# asserv.net
KiCad netlist of a schematic drawn in EAGLE
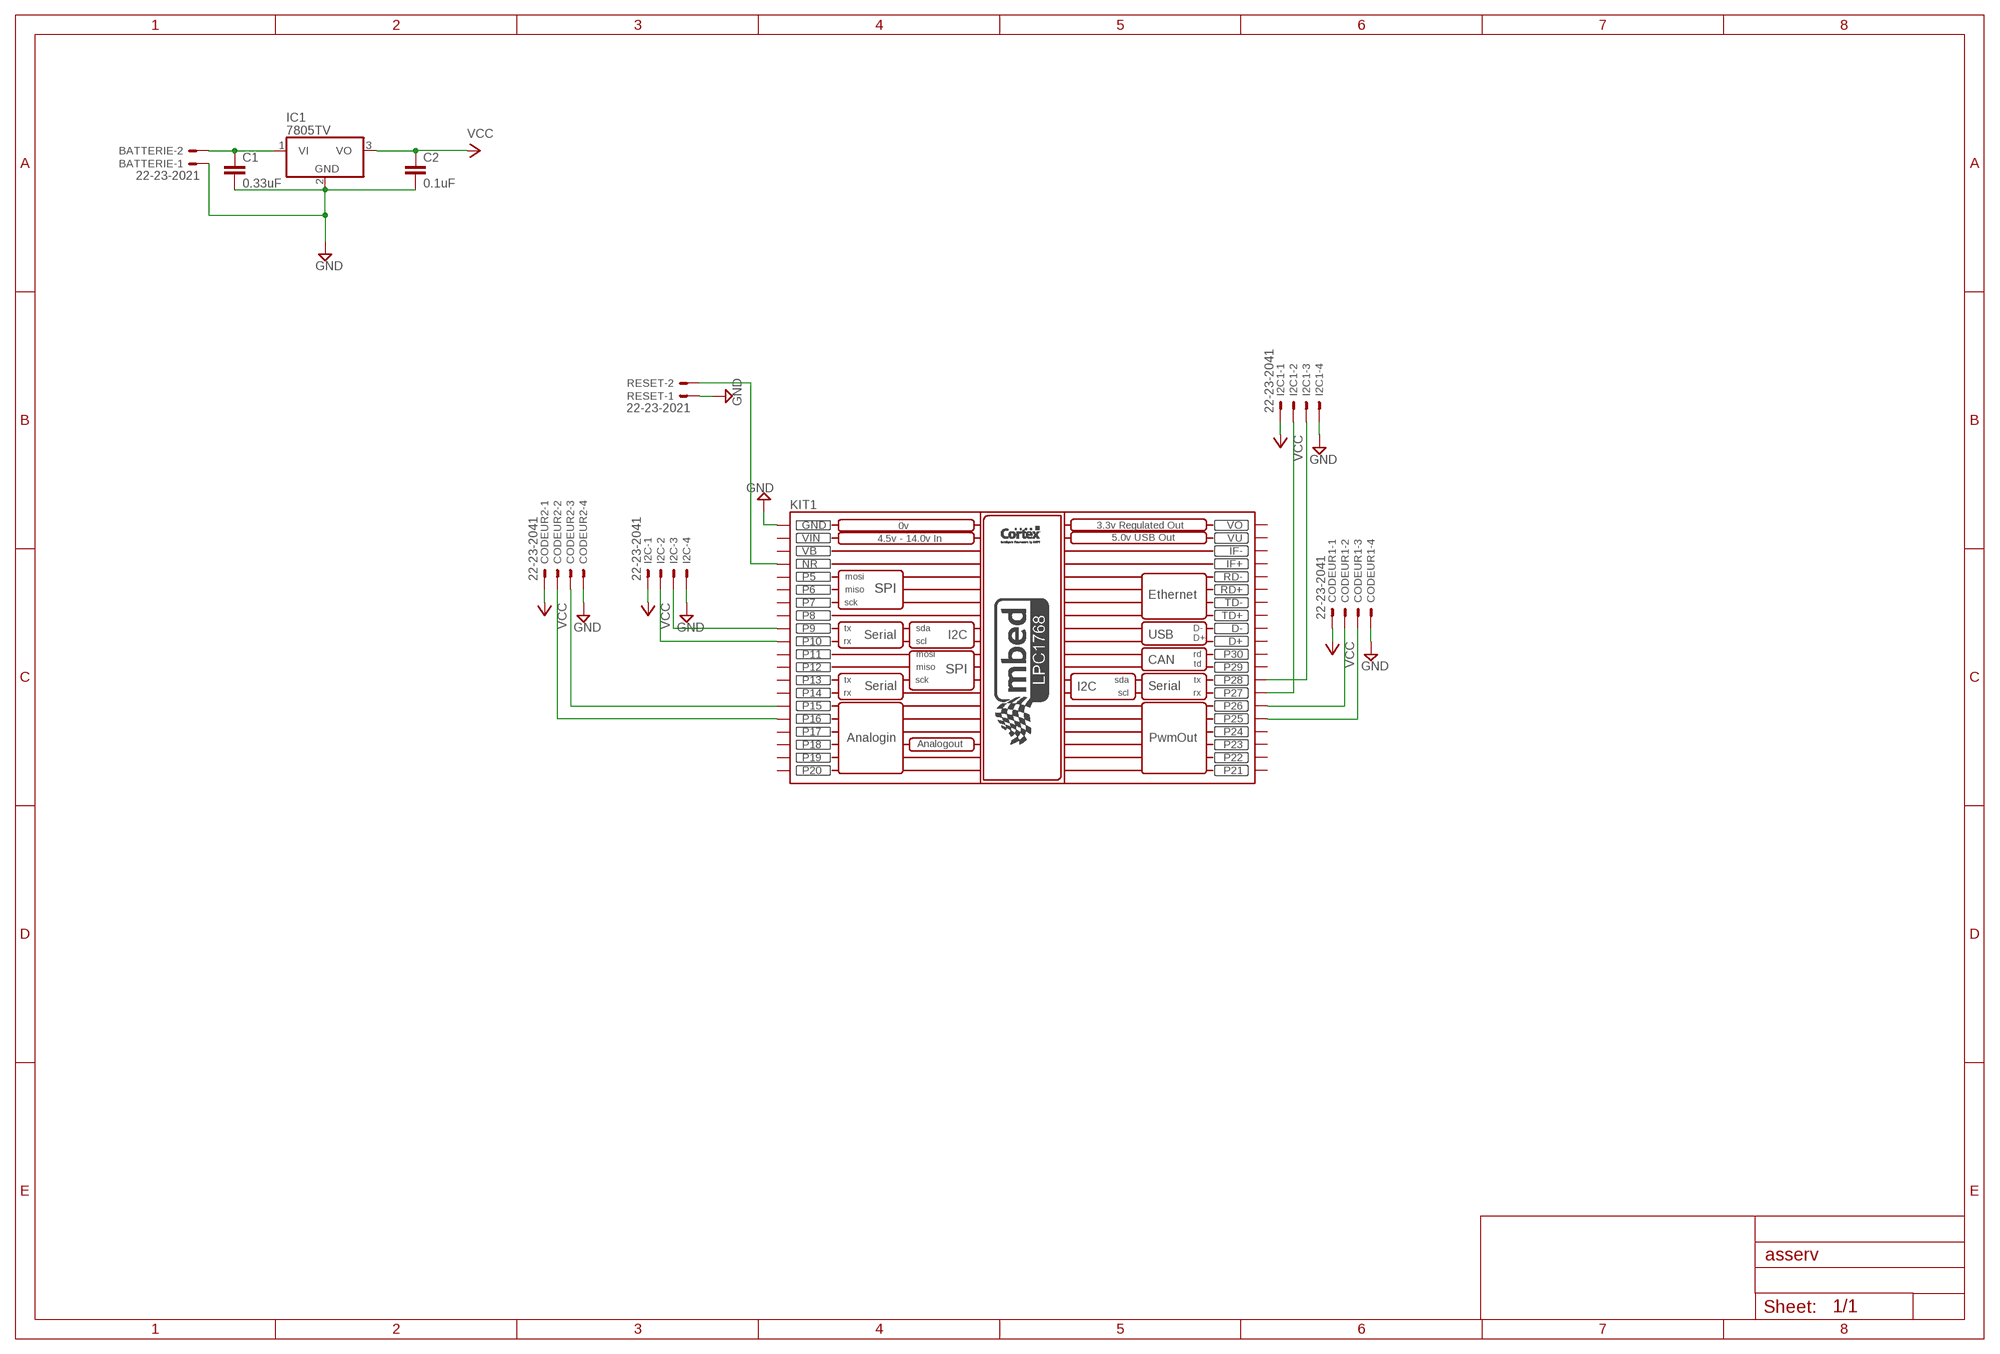
[diagram p0: schematic, sheet 1]

(export (version "E")
  (design (tool "Eeschema 10.0.6"))
  (components
    (comp (ref "BATTERIE")
      (value "22-23-2021")
      (footprint "eagle-import:22-23-2021")
      (fields (field (name "MF") "MOLEX"))
      (libsource (lib "eagle-import") (part "22-23-2021"))
    )
    (comp (ref "C1")
      (value "0.33uF")
      (footprint "eagle-import:C5B2.5")
      (libsource (lib "eagle-import") (part "C5/2.5"))
    )
    (comp (ref "C2")
      (value "0.1uF")
      (footprint "eagle-import:C5B2.5")
      (libsource (lib "eagle-import") (part "C5/2.5"))
    )
    (comp (ref "CODEUR1")
      (value "22-23-2041")
      (footprint "eagle-import:22-23-2041")
      (fields (field (name "MF") "MOLEX"))
      (libsource (lib "eagle-import") (part "22-23-2041"))
    )
    (comp (ref "CODEUR2")
      (value "22-23-2041")
      (footprint "eagle-import:22-23-2041")
      (fields (field (name "MF") "MOLEX"))
      (libsource (lib "eagle-import") (part "22-23-2041"))
    )
    (comp (ref "I2C")
      (value "22-23-2041")
      (footprint "eagle-import:22-23-2041")
      (fields (field (name "MF") "MOLEX"))
      (libsource (lib "eagle-import") (part "22-23-2041"))
    )
    (comp (ref "I2C1")
      (value "22-23-2041")
      (footprint "eagle-import:22-23-2041")
      (fields (field (name "MF") "MOLEX"))
      (libsource (lib "eagle-import") (part "22-23-2041"))
    )
    (comp (ref "IC1")
      (value "7805TV")
      (footprint "eagle-import:TO220V")
      (libsource (lib "eagle-import") (part "78TV05"))
    )
    (comp (ref "KIT1")
      (value "MBED_NXP_LPC1768")
      (footprint "eagle-import:MBED-KIT")
      (libsource (lib "eagle-import") (part "MBED_NXP_LPC1768"))
    )
    (comp (ref "RESET")
      (value "22-23-2021")
      (footprint "eagle-import:22-23-2021")
      (fields (field (name "MF") "MOLEX"))
      (libsource (lib "eagle-import") (part "22-23-2021"))
    )
  )
  (nets
    (net (code "1") (name "/VB") (class "Default")
      (node (ref "KIT1") (pin "VB") (pinfunction "VB_VB") (pintype "power_in"))
    )
    (net (code "2") (name "/VIN") (class "Default")
      (node (ref "KIT1") (pin "VIN") (pinfunction "VIN_VIN") (pintype "power_in"))
    )
    (net (code "3") (name "/VO") (class "Default")
      (node (ref "KIT1") (pin "VOUT") (pinfunction "VO_VOUT") (pintype "power_in"))
    )
    (net (code "4") (name "/VU") (class "Default")
      (node (ref "KIT1") (pin "VU") (pinfunction "VU_VU") (pintype "power_in"))
    )
    (net (code "5") (name "GND") (class "Default")
      (node (ref "BATTERIE") (pin "1") (pinfunction "S_1") (pintype "passive"))
      (node (ref "C1") (pin "2") (pinfunction "2_2") (pintype "passive"))
      (node (ref "C2") (pin "2") (pinfunction "2_2") (pintype "passive"))
      (node (ref "CODEUR1") (pin "4") (pinfunction "S_4") (pintype "passive"))
      (node (ref "CODEUR2") (pin "4") (pinfunction "S_4") (pintype "passive"))
      (node (ref "I2C") (pin "4") (pinfunction "S_4") (pintype "passive"))
      (node (ref "I2C1") (pin "4") (pinfunction "S_4") (pintype "passive"))
      (node (ref "IC1") (pin "2") (pinfunction "GND_2") (pintype "passive"))
      (node (ref "KIT1") (pin "GND") (pinfunction "GND_GND") (pintype "power_in"))
      (node (ref "RESET") (pin "1") (pinfunction "S_1") (pintype "passive"))
    )
    (net (code "6") (name "Net-(BATTERIEB-S)") (class "Default")
      (node (ref "BATTERIE") (pin "2") (pinfunction "S_2") (pintype "passive"))
      (node (ref "C1") (pin "1") (pinfunction "1_1") (pintype "passive"))
      (node (ref "IC1") (pin "1") (pinfunction "VI_1") (pintype "input"))
    )
    (net (code "7") (name "Net-(CODEUR1B-S)") (class "Default")
      (node (ref "CODEUR1") (pin "2") (pinfunction "S_2") (pintype "passive"))
      (node (ref "KIT1") (pin "P$26") (pinfunction "P26_P$26") (pintype "bidirectional"))
    )
    (net (code "8") (name "Net-(CODEUR1C-S)") (class "Default")
      (node (ref "CODEUR1") (pin "3") (pinfunction "S_3") (pintype "passive"))
      (node (ref "KIT1") (pin "P$25") (pinfunction "P25_P$25") (pintype "bidirectional"))
    )
    (net (code "9") (name "Net-(CODEUR2B-S)") (class "Default")
      (node (ref "CODEUR2") (pin "2") (pinfunction "S_2") (pintype "passive"))
      (node (ref "KIT1") (pin "P$16") (pinfunction "P16_P$16") (pintype "bidirectional"))
    )
    (net (code "10") (name "Net-(CODEUR2C-S)") (class "Default")
      (node (ref "CODEUR2") (pin "3") (pinfunction "S_3") (pintype "passive"))
      (node (ref "KIT1") (pin "P$15") (pinfunction "P15_P$15") (pintype "bidirectional"))
    )
    (net (code "11") (name "Net-(I2C1B-S)") (class "Default")
      (node (ref "I2C1") (pin "2") (pinfunction "S_2") (pintype "passive"))
      (node (ref "KIT1") (pin "P$27") (pinfunction "P27_P$27") (pintype "bidirectional"))
    )
    (net (code "12") (name "Net-(I2C1C-S)") (class "Default")
      (node (ref "I2C1") (pin "3") (pinfunction "S_3") (pintype "passive"))
      (node (ref "KIT1") (pin "P$28") (pinfunction "P28_P$28") (pintype "bidirectional"))
    )
    (net (code "13") (name "Net-(I2CB-S)") (class "Default")
      (node (ref "I2C") (pin "2") (pinfunction "S_2") (pintype "passive"))
      (node (ref "KIT1") (pin "P$10") (pinfunction "P10_P$10") (pintype "bidirectional"))
    )
    (net (code "14") (name "Net-(I2CC-S)") (class "Default")
      (node (ref "I2C") (pin "3") (pinfunction "S_3") (pintype "passive"))
      (node (ref "KIT1") (pin "P$9") (pinfunction "P9_P$9") (pintype "bidirectional"))
    )
    (net (code "15") (name "Net-(RESETB-S)") (class "Default")
      (node (ref "KIT1") (pin "NR") (pinfunction "NR_NR") (pintype "power_in"))
      (node (ref "RESET") (pin "2") (pinfunction "S_2") (pintype "passive"))
    )
    (net (code "16") (name "VCC") (class "Default")
      (node (ref "C2") (pin "1") (pinfunction "1_1") (pintype "passive"))
      (node (ref "CODEUR1") (pin "1") (pinfunction "S_1") (pintype "passive"))
      (node (ref "CODEUR2") (pin "1") (pinfunction "S_1") (pintype "passive"))
      (node (ref "I2C") (pin "1") (pinfunction "S_1") (pintype "passive"))
      (node (ref "I2C1") (pin "1") (pinfunction "S_1") (pintype "passive"))
      (node (ref "IC1") (pin "3") (pinfunction "VO_3") (pintype "passive"))
    )
    (net (code "17") (name "unconnected-(KIT1-P5-PadP$5)") (class "Default")
      (node (ref "KIT1") (pin "P$5") (pinfunction "P5_P$5") (pintype "bidirectional"))
    )
    (net (code "18") (name "unconnected-(KIT1-P6-PadP$6)") (class "Default")
      (node (ref "KIT1") (pin "P$6") (pinfunction "P6_P$6") (pintype "bidirectional"))
    )
    (net (code "19") (name "unconnected-(KIT1-P7-PadP$7)") (class "Default")
      (node (ref "KIT1") (pin "P$7") (pinfunction "P7_P$7") (pintype "bidirectional"))
    )
    (net (code "20") (name "unconnected-(KIT1-P8-PadP$8)") (class "Default")
      (node (ref "KIT1") (pin "P$8") (pinfunction "P8_P$8") (pintype "bidirectional"))
    )
    (net (code "21") (name "unconnected-(KIT1-P11-PadP$11)") (class "Default")
      (node (ref "KIT1") (pin "P$11") (pinfunction "P11_P$11") (pintype "bidirectional"))
    )
    (net (code "22") (name "unconnected-(KIT1-P12-PadP$12)") (class "Default")
      (node (ref "KIT1") (pin "P$12") (pinfunction "P12_P$12") (pintype "bidirectional"))
    )
    (net (code "23") (name "unconnected-(KIT1-P13-PadP$13)") (class "Default")
      (node (ref "KIT1") (pin "P$13") (pinfunction "P13_P$13") (pintype "bidirectional"))
    )
    (net (code "24") (name "unconnected-(KIT1-P14-PadP$14)") (class "Default")
      (node (ref "KIT1") (pin "P$14") (pinfunction "P14_P$14") (pintype "bidirectional"))
    )
    (net (code "25") (name "unconnected-(KIT1-P17-PadP$17)") (class "Default")
      (node (ref "KIT1") (pin "P$17") (pinfunction "P17_P$17") (pintype "bidirectional"))
    )
    (net (code "26") (name "unconnected-(KIT1-P18-PadP$18)") (class "Default")
      (node (ref "KIT1") (pin "P$18") (pinfunction "P18_P$18") (pintype "bidirectional"))
    )
    (net (code "27") (name "unconnected-(KIT1-P19-PadP$19)") (class "Default")
      (node (ref "KIT1") (pin "P$19") (pinfunction "P19_P$19") (pintype "bidirectional"))
    )
    (net (code "28") (name "unconnected-(KIT1-P20-PadP$20)") (class "Default")
      (node (ref "KIT1") (pin "P$20") (pinfunction "P20_P$20") (pintype "bidirectional"))
    )
    (net (code "29") (name "unconnected-(KIT1-P21-PadP$21)") (class "Default")
      (node (ref "KIT1") (pin "P$21") (pinfunction "P21_P$21") (pintype "bidirectional"))
    )
    (net (code "30") (name "unconnected-(KIT1-P22-PadP$22)") (class "Default")
      (node (ref "KIT1") (pin "P$22") (pinfunction "P22_P$22") (pintype "bidirectional"))
    )
    (net (code "31") (name "unconnected-(KIT1-P23-PadP$23)") (class "Default")
      (node (ref "KIT1") (pin "P$23") (pinfunction "P23_P$23") (pintype "bidirectional"))
    )
    (net (code "32") (name "unconnected-(KIT1-P24-PadP$24)") (class "Default")
      (node (ref "KIT1") (pin "P$24") (pinfunction "P24_P$24") (pintype "bidirectional"))
    )
    (net (code "33") (name "unconnected-(KIT1-P29-PadP$29)") (class "Default")
      (node (ref "KIT1") (pin "P$29") (pinfunction "P29_P$29") (pintype "bidirectional"))
    )
    (net (code "34") (name "unconnected-(KIT1-P30-PadP$30)") (class "Default")
      (node (ref "KIT1") (pin "P$30") (pinfunction "P30_P$30") (pintype "bidirectional"))
    )
    (net (code "35") (name "unconnected-(KIT1-PadD+)") (class "Default")
      (node (ref "KIT1") (pin "D+") (pinfunction "D+_D+") (pintype "bidirectional"))
    )
    (net (code "36") (name "unconnected-(KIT1-PadD-)") (class "Default")
      (node (ref "KIT1") (pin "D-") (pinfunction "D-_D-") (pintype "bidirectional"))
    )
    (net (code "37") (name "unconnected-(KIT1-PadIF+)") (class "Default")
      (node (ref "KIT1") (pin "IF+") (pinfunction "IF+_IF+") (pintype "bidirectional"))
    )
    (net (code "38") (name "unconnected-(KIT1-PadIF-)") (class "Default")
      (node (ref "KIT1") (pin "IF-") (pinfunction "IF-_IF-") (pintype "bidirectional"))
    )
    (net (code "39") (name "unconnected-(KIT1-PadRD+)") (class "Default")
      (node (ref "KIT1") (pin "RD+") (pinfunction "RD+_RD+") (pintype "bidirectional"))
    )
    (net (code "40") (name "unconnected-(KIT1-PadRD-)") (class "Default")
      (node (ref "KIT1") (pin "RD-") (pinfunction "RD-_RD-") (pintype "bidirectional"))
    )
    (net (code "41") (name "unconnected-(KIT1-PadTD+)") (class "Default")
      (node (ref "KIT1") (pin "TD+") (pinfunction "TD+_TD+") (pintype "bidirectional"))
    )
    (net (code "42") (name "unconnected-(KIT1-PadTD-)") (class "Default")
      (node (ref "KIT1") (pin "TD-") (pinfunction "TD-_TD-") (pintype "bidirectional"))
    )
  )
)
